# dynafeather.net
KiCad netlist of a schematic drawn in EAGLE
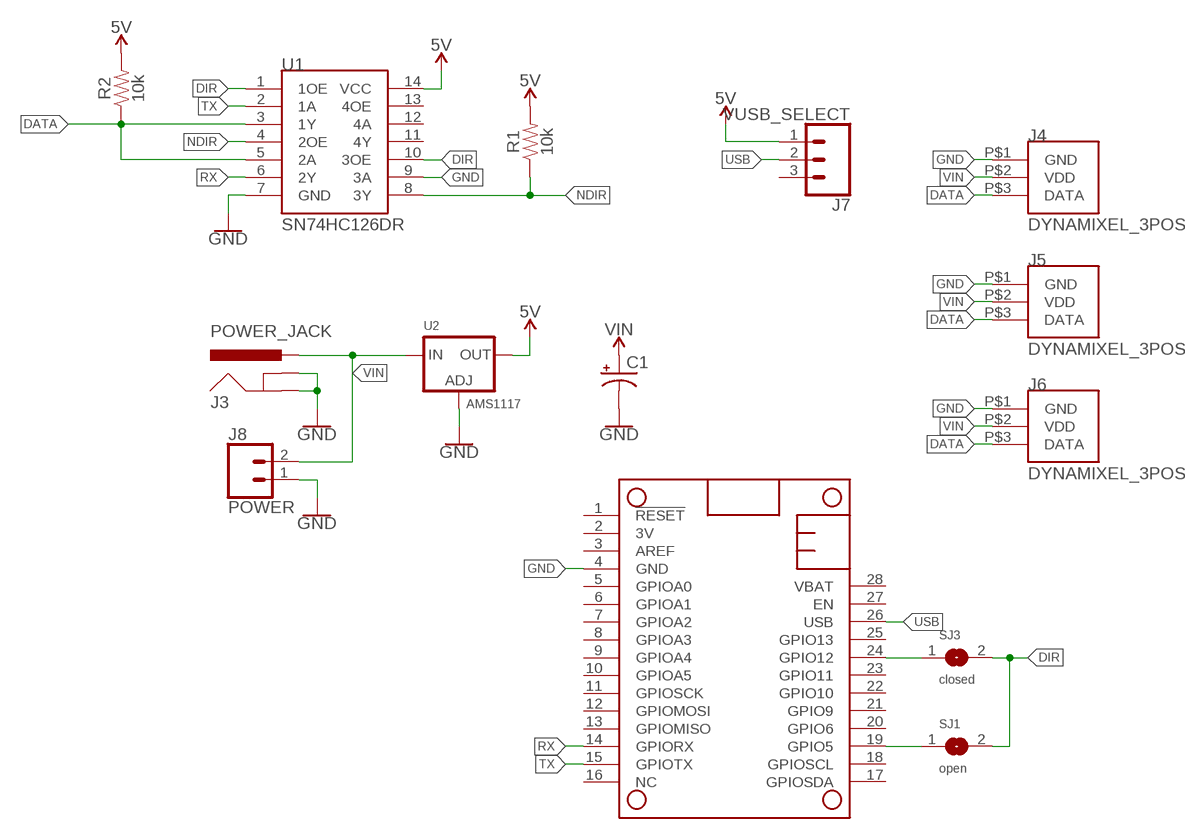
[diagram p0: schematic, sheet 1]

(export (version "E")
  (design (tool "Eeschema 10.0.6"))
  (components
    (comp (ref "C1")
      (value "ALUM_CAP_0605")
      (footprint "eagle-import:153CLV-0605")
      (libsource (lib "eagle-import") (part "ALUM_CAP_0605"))
    )
    (comp (ref "J3")
      (value "POWER_JACK")
      (footprint "eagle-import:POWER_JACK_PTH")
      (libsource (lib "eagle-import") (part "POWER_JACK"))
    )
    (comp (ref "J4")
      (value "DYNAMIXEL_3POS")
      (footprint "eagle-import:CONN-MSPOX-3POS")
      (libsource (lib "eagle-import") (part "DYNAMIXEL_3POS"))
    )
    (comp (ref "J5")
      (value "DYNAMIXEL_3POS")
      (footprint "eagle-import:CONN-MSPOX-3POS")
      (libsource (lib "eagle-import") (part "DYNAMIXEL_3POS"))
    )
    (comp (ref "J6")
      (value "DYNAMIXEL_3POS")
      (footprint "eagle-import:CONN-MSPOX-3POS")
      (libsource (lib "eagle-import") (part "DYNAMIXEL_3POS"))
    )
    (comp (ref "J7")
      (value "VUSB_SELECT")
      (footprint "eagle-import:1X03_LOCK")
      (libsource (lib "eagle-import") (part "CONN_03LOCK"))
    )
    (comp (ref "J8")
      (value "POWER")
      (footprint "eagle-import:SCREWTERMINAL-3.5MM-2")
      (libsource (lib "eagle-import") (part "CONN_023.5MM"))
    )
    (comp (ref "MS1")
      (value "FEATHERWING")
      (footprint "eagle-import:FEATHERWING")
      (libsource (lib "eagle-import") (part "FEATHERWING"))
    )
    (comp (ref "R1")
      (value "10k")
      (footprint "eagle-import:0603")
      (libsource (lib "eagle-import") (part "10KOHM-0603-1/10W-1%"))
    )
    (comp (ref "R2")
      (value "10k")
      (footprint "eagle-import:0603")
      (libsource (lib "eagle-import") (part "10KOHM-0603-1/10W-1%"))
    )
    (comp (ref "SJ1")
      (value "open")
      (footprint "eagle-import:SOLDERJUMPER_REFLOW")
      (libsource (lib "eagle-import") (part "SOLDERJUMPERREFLOW"))
    )
    (comp (ref "SJ3")
      (value "closed")
      (footprint "eagle-import:SOLDERJUMPER_CLOSEDWIRE")
      (libsource (lib "eagle-import") (part "SOLDERJUMPERCLOSED"))
    )
    (comp (ref "U1")
      (value "SN74HC126DR")
      (footprint "eagle-import:SOP14")
      (libsource (lib "eagle-import") (part "SN74HC126DR"))
    )
    (comp (ref "U2")
      (value "AMS1117")
      (footprint "eagle-import:SOT223-R")
      (libsource (lib "eagle-import") (part "LM1117SOT223-REFLOW"))
    )
  )
  (nets
    (net (code "1") (name "/3V") (class "Default")
      (node (ref "MS1") (pin "2") (pinfunction "3V_2") (pintype "power_in"))
    )
    (net (code "2") (name "/VBAT") (class "Default")
      (node (ref "MS1") (pin "28") (pinfunction "VBAT_28") (pintype "power_in"))
    )
    (net (code "3") (name "5V") (class "Default")
      (node (ref "J7") (pin "1") (pinfunction "1_1") (pintype "passive"))
      (node (ref "R1") (pin "2") (pinfunction "2_2") (pintype "passive"))
      (node (ref "R2") (pin "2") (pinfunction "2_2") (pintype "passive"))
      (node (ref "U1") (pin "14") (pinfunction "VCC_14") (pintype "bidirectional"))
      (node (ref "U2") (pin "2") (pinfunction "OUT_2") (pintype "passive"))
      (node (ref "U2") (pin "4") (pinfunction "OUT_4") (pintype "passive"))
    )
    (net (code "4") (name "DATA") (class "Default")
      (node (ref "J4") (pin "P$3") (pinfunction "DATA_P$3") (pintype "bidirectional"))
      (node (ref "J5") (pin "P$3") (pinfunction "DATA_P$3") (pintype "bidirectional"))
      (node (ref "J6") (pin "P$3") (pinfunction "DATA_P$3") (pintype "bidirectional"))
      (node (ref "R2") (pin "1") (pinfunction "1_1") (pintype "passive"))
      (node (ref "U1") (pin "3") (pinfunction "1Y_3") (pintype "bidirectional"))
      (node (ref "U1") (pin "5") (pinfunction "2A_5") (pintype "bidirectional"))
    )
    (net (code "5") (name "DIR") (class "Default")
      (node (ref "SJ1") (pin "2") (pinfunction "2_2") (pintype "passive"))
      (node (ref "SJ3") (pin "2") (pinfunction "2_2") (pintype "passive"))
      (node (ref "U1") (pin "1") (pinfunction "1OE_1") (pintype "bidirectional"))
      (node (ref "U1") (pin "10") (pinfunction "3OE_10") (pintype "bidirectional"))
    )
    (net (code "6") (name "GND") (class "Default")
      (node (ref "C1") (pin "-") (pinfunction "-_-") (pintype "passive"))
      (node (ref "J3") (pin "GND") (pinfunction "GND_GND") (pintype "bidirectional"))
      (node (ref "J3") (pin "GNDBREAK") (pinfunction "GNDBREAK_GNDBREAK") (pintype "bidirectional"))
      (node (ref "J4") (pin "P$1") (pinfunction "GND_P$1") (pintype "bidirectional"))
      (node (ref "J5") (pin "P$1") (pinfunction "GND_P$1") (pintype "bidirectional"))
      (node (ref "J6") (pin "P$1") (pinfunction "GND_P$1") (pintype "bidirectional"))
      (node (ref "J8") (pin "1") (pinfunction "1_1") (pintype "passive"))
      (node (ref "MS1") (pin "4") (pinfunction "GND_4") (pintype "power_in"))
      (node (ref "U1") (pin "7") (pinfunction "GND_7") (pintype "bidirectional"))
      (node (ref "U1") (pin "9") (pinfunction "3A_9") (pintype "bidirectional"))
      (node (ref "U2") (pin "1") (pinfunction "ADJ_1") (pintype "input"))
    )
    (net (code "7") (name "NDIR") (class "Default")
      (node (ref "R1") (pin "1") (pinfunction "1_1") (pintype "passive"))
      (node (ref "U1") (pin "4") (pinfunction "2OE_4") (pintype "bidirectional"))
      (node (ref "U1") (pin "8") (pinfunction "3Y_8") (pintype "bidirectional"))
    )
    (net (code "8") (name "Net-(MS1-GPIO5)") (class "Default")
      (node (ref "MS1") (pin "19") (pinfunction "GPIO5_19") (pintype "bidirectional"))
      (node (ref "SJ1") (pin "1") (pinfunction "1_1") (pintype "passive"))
    )
    (net (code "9") (name "Net-(MS1-GPIO12)") (class "Default")
      (node (ref "MS1") (pin "24") (pinfunction "GPIO12_24") (pintype "bidirectional"))
      (node (ref "SJ3") (pin "1") (pinfunction "1_1") (pintype "passive"))
    )
    (net (code "10") (name "RX") (class "Default")
      (node (ref "MS1") (pin "14") (pinfunction "GPIORX_14") (pintype "bidirectional"))
      (node (ref "U1") (pin "6") (pinfunction "2Y_6") (pintype "bidirectional"))
    )
    (net (code "11") (name "TX") (class "Default")
      (node (ref "MS1") (pin "15") (pinfunction "GPIOTX_15") (pintype "bidirectional"))
      (node (ref "U1") (pin "2") (pinfunction "1A_2") (pintype "bidirectional"))
    )
    (net (code "12") (name "USB") (class "Default")
      (node (ref "J7") (pin "2") (pinfunction "2_2") (pintype "passive"))
      (node (ref "MS1") (pin "26") (pinfunction "USB_26") (pintype "power_in"))
    )
    (net (code "13") (name "VIN") (class "Default")
      (node (ref "C1") (pin "+") (pinfunction "+_+") (pintype "passive"))
      (node (ref "J3") (pin "PWR") (pinfunction "PWR_PWR") (pintype "bidirectional"))
      (node (ref "J4") (pin "P$2") (pinfunction "VDD_P$2") (pintype "bidirectional"))
      (node (ref "J5") (pin "P$2") (pinfunction "VDD_P$2") (pintype "bidirectional"))
      (node (ref "J6") (pin "P$2") (pinfunction "VDD_P$2") (pintype "bidirectional"))
      (node (ref "J8") (pin "2") (pinfunction "2_2") (pintype "passive"))
      (node (ref "U2") (pin "3") (pinfunction "IN_3") (pintype "input"))
    )
    (net (code "14") (name "unconnected-(J7-Pad3)") (class "Default")
      (node (ref "J7") (pin "3") (pinfunction "3_3") (pintype "passive"))
    )
    (net (code "15") (name "unconnected-(MS1-AREF-Pad3)") (class "Default")
      (node (ref "MS1") (pin "3") (pinfunction "AREF_3") (pintype "passive"))
    )
    (net (code "16") (name "unconnected-(MS1-EN-Pad27)") (class "Default")
      (node (ref "MS1") (pin "27") (pinfunction "EN_27") (pintype "passive"))
    )
    (net (code "17") (name "unconnected-(MS1-GPIO6-Pad20)") (class "Default")
      (node (ref "MS1") (pin "20") (pinfunction "GPIO6_20") (pintype "bidirectional"))
    )
    (net (code "18") (name "unconnected-(MS1-GPIO9-Pad21)") (class "Default")
      (node (ref "MS1") (pin "21") (pinfunction "GPIO9_21") (pintype "bidirectional"))
    )
    (net (code "19") (name "unconnected-(MS1-GPIO10-Pad22)") (class "Default")
      (node (ref "MS1") (pin "22") (pinfunction "GPIO10_22") (pintype "bidirectional"))
    )
    (net (code "20") (name "unconnected-(MS1-GPIO11-Pad23)") (class "Default")
      (node (ref "MS1") (pin "23") (pinfunction "GPIO11_23") (pintype "bidirectional"))
    )
    (net (code "21") (name "unconnected-(MS1-GPIO13-Pad25)") (class "Default")
      (node (ref "MS1") (pin "25") (pinfunction "GPIO13_25") (pintype "bidirectional"))
    )
    (net (code "22") (name "unconnected-(MS1-GPIOA0-Pad5)") (class "Default")
      (node (ref "MS1") (pin "5") (pinfunction "GPIOA0_5") (pintype "bidirectional"))
    )
    (net (code "23") (name "unconnected-(MS1-GPIOA1-Pad6)") (class "Default")
      (node (ref "MS1") (pin "6") (pinfunction "GPIOA1_6") (pintype "bidirectional"))
    )
    (net (code "24") (name "unconnected-(MS1-GPIOA2-Pad7)") (class "Default")
      (node (ref "MS1") (pin "7") (pinfunction "GPIOA2_7") (pintype "bidirectional"))
    )
    (net (code "25") (name "unconnected-(MS1-GPIOA3-Pad8)") (class "Default")
      (node (ref "MS1") (pin "8") (pinfunction "GPIOA3_8") (pintype "bidirectional"))
    )
    (net (code "26") (name "unconnected-(MS1-GPIOA4-Pad9)") (class "Default")
      (node (ref "MS1") (pin "9") (pinfunction "GPIOA4_9") (pintype "bidirectional"))
    )
    (net (code "27") (name "unconnected-(MS1-GPIOA5-Pad10)") (class "Default")
      (node (ref "MS1") (pin "10") (pinfunction "GPIOA5_10") (pintype "bidirectional"))
    )
    (net (code "28") (name "unconnected-(MS1-GPIOMISO-Pad13)") (class "Default")
      (node (ref "MS1") (pin "13") (pinfunction "GPIOMISO_13") (pintype "bidirectional"))
    )
    (net (code "29") (name "unconnected-(MS1-GPIOMOSI-Pad12)") (class "Default")
      (node (ref "MS1") (pin "12") (pinfunction "GPIOMOSI_12") (pintype "bidirectional"))
    )
    (net (code "30") (name "unconnected-(MS1-GPIOSCK-Pad11)") (class "Default")
      (node (ref "MS1") (pin "11") (pinfunction "GPIOSCK_11") (pintype "bidirectional"))
    )
    (net (code "31") (name "unconnected-(MS1-GPIOSCL-Pad18)") (class "Default")
      (node (ref "MS1") (pin "18") (pinfunction "GPIOSCL_18") (pintype "bidirectional"))
    )
    (net (code "32") (name "unconnected-(MS1-GPIOSDA-Pad17)") (class "Default")
      (node (ref "MS1") (pin "17") (pinfunction "GPIOSDA_17") (pintype "bidirectional"))
    )
    (net (code "33") (name "unconnected-(MS1-NC-Pad16)") (class "Default")
      (node (ref "MS1") (pin "16") (pinfunction "NC_16") (pintype "passive"))
    )
    (net (code "34") (name "unconnected-(MS1-~{RESET}-Pad1)") (class "Default")
      (node (ref "MS1") (pin "1") (pinfunction "~{RESET}_1") (pintype "input"))
    )
    (net (code "35") (name "unconnected-(U1-4A-Pad12)") (class "Default")
      (node (ref "U1") (pin "12") (pinfunction "4A_12") (pintype "bidirectional"))
    )
    (net (code "36") (name "unconnected-(U1-4OE-Pad13)") (class "Default")
      (node (ref "U1") (pin "13") (pinfunction "4OE_13") (pintype "bidirectional"))
    )
    (net (code "37") (name "unconnected-(U1-4Y-Pad11)") (class "Default")
      (node (ref "U1") (pin "11") (pinfunction "4Y_11") (pintype "bidirectional"))
    )
  )
)
